# gadapter.net
KiCad netlist of a schematic drawn in Altium Designer
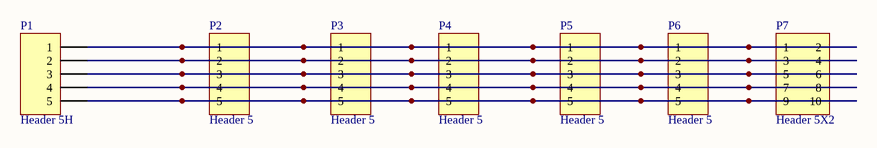
[diagram p0: gadapter.SchDoc]

(export (version "E")
  (design (tool "Eeschema 10.0.6"))
  (components
    (comp (ref "P1")
      (value "Header 5H")
      (footprint "HDR1X5H")
      (description "Header, 5-Pin, Right Angle")
      (fields (field (name "PUBLISHER") "Altium Limited"))
      (libsource (lib "Miscellaneous Connectors") (part "Header 5H"))
    )
    (comp (ref "P2")
      (value "Header 5")
      (footprint "HDR1X5")
      (description "Header, 5-Pin")
      (fields (field (name "PUBLISHER") "Altium Limited"))
      (libsource (lib "Miscellaneous Connectors") (part "Header 5"))
    )
    (comp (ref "P3")
      (value "Header 5")
      (footprint "HDR1X5")
      (description "Header, 5-Pin")
      (fields (field (name "PUBLISHER") "Altium Limited"))
      (libsource (lib "Miscellaneous Connectors") (part "Header 5"))
    )
    (comp (ref "P4")
      (value "Header 5")
      (footprint "HDR1X5")
      (description "Header, 5-Pin")
      (fields (field (name "PUBLISHER") "Altium Limited"))
      (libsource (lib "Miscellaneous Connectors") (part "Header 5"))
    )
    (comp (ref "P5")
      (value "Header 5")
      (footprint "HDR1X5")
      (description "Header, 5-Pin")
      (fields (field (name "PUBLISHER") "Altium Limited"))
      (libsource (lib "Miscellaneous Connectors") (part "Header 5"))
    )
    (comp (ref "P6")
      (value "Header 5")
      (footprint "HDR1X5")
      (description "Header, 5-Pin")
      (fields (field (name "PUBLISHER") "Altium Limited"))
      (libsource (lib "Miscellaneous Connectors") (part "Header 5"))
    )
    (comp (ref "P7")
      (value "Header 5X2")
      (footprint "HDR2X5")
      (description "Header, 5-Pin, Dual row")
      (fields (field (name "PUBLISHER") "Altium Limited"))
      (libsource (lib "Miscellaneous Connectors") (part "Header 5X2"))
    )
  )
  (nets
    (net (code "1") (name "Net-(P1-Pad1)") (class "Default")
      (node (ref "P1") (pin "1") (pinfunction "1_1") (pintype "passive"))
      (node (ref "P2") (pin "1") (pinfunction "1_1") (pintype "passive"))
      (node (ref "P3") (pin "1") (pinfunction "1_1") (pintype "passive"))
      (node (ref "P4") (pin "1") (pinfunction "1_1") (pintype "passive"))
      (node (ref "P5") (pin "1") (pinfunction "1_1") (pintype "passive"))
      (node (ref "P6") (pin "1") (pinfunction "1_1") (pintype "passive"))
      (node (ref "P7") (pin "1") (pinfunction "1_1") (pintype "passive"))
      (node (ref "P7") (pin "2") (pinfunction "2_2") (pintype "passive"))
    )
    (net (code "2") (name "Net-(P1-Pad2)") (class "Default")
      (node (ref "P1") (pin "2") (pinfunction "2_2") (pintype "passive"))
      (node (ref "P2") (pin "2") (pinfunction "2_2") (pintype "passive"))
      (node (ref "P3") (pin "2") (pinfunction "2_2") (pintype "passive"))
      (node (ref "P4") (pin "2") (pinfunction "2_2") (pintype "passive"))
      (node (ref "P5") (pin "2") (pinfunction "2_2") (pintype "passive"))
      (node (ref "P6") (pin "2") (pinfunction "2_2") (pintype "passive"))
      (node (ref "P7") (pin "3") (pinfunction "3_3") (pintype "passive"))
      (node (ref "P7") (pin "4") (pinfunction "4_4") (pintype "passive"))
    )
    (net (code "3") (name "Net-(P1-Pad3)") (class "Default")
      (node (ref "P1") (pin "3") (pinfunction "3_3") (pintype "passive"))
      (node (ref "P2") (pin "3") (pinfunction "3_3") (pintype "passive"))
      (node (ref "P3") (pin "3") (pinfunction "3_3") (pintype "passive"))
      (node (ref "P4") (pin "3") (pinfunction "3_3") (pintype "passive"))
      (node (ref "P5") (pin "3") (pinfunction "3_3") (pintype "passive"))
      (node (ref "P6") (pin "3") (pinfunction "3_3") (pintype "passive"))
      (node (ref "P7") (pin "5") (pinfunction "5_5") (pintype "passive"))
      (node (ref "P7") (pin "6") (pinfunction "6_6") (pintype "passive"))
    )
    (net (code "4") (name "Net-(P1-Pad4)") (class "Default")
      (node (ref "P1") (pin "4") (pinfunction "4_4") (pintype "passive"))
      (node (ref "P2") (pin "4") (pinfunction "4_4") (pintype "passive"))
      (node (ref "P3") (pin "4") (pinfunction "4_4") (pintype "passive"))
      (node (ref "P4") (pin "4") (pinfunction "4_4") (pintype "passive"))
      (node (ref "P5") (pin "4") (pinfunction "4_4") (pintype "passive"))
      (node (ref "P6") (pin "4") (pinfunction "4_4") (pintype "passive"))
      (node (ref "P7") (pin "7") (pinfunction "7_7") (pintype "passive"))
      (node (ref "P7") (pin "8") (pinfunction "8_8") (pintype "passive"))
    )
    (net (code "5") (name "Net-(P1-Pad5)") (class "Default")
      (node (ref "P1") (pin "5") (pinfunction "5_5") (pintype "passive"))
      (node (ref "P2") (pin "5") (pinfunction "5_5") (pintype "passive"))
      (node (ref "P3") (pin "5") (pinfunction "5_5") (pintype "passive"))
      (node (ref "P4") (pin "5") (pinfunction "5_5") (pintype "passive"))
      (node (ref "P5") (pin "5") (pinfunction "5_5") (pintype "passive"))
      (node (ref "P6") (pin "5") (pinfunction "5_5") (pintype "passive"))
      (node (ref "P7") (pin "10") (pinfunction "10_10") (pintype "passive"))
      (node (ref "P7") (pin "9") (pinfunction "9_9") (pintype "passive"))
    )
  )
)
